# LDO.net
KiCad netlist of a schematic drawn in Altium Designer
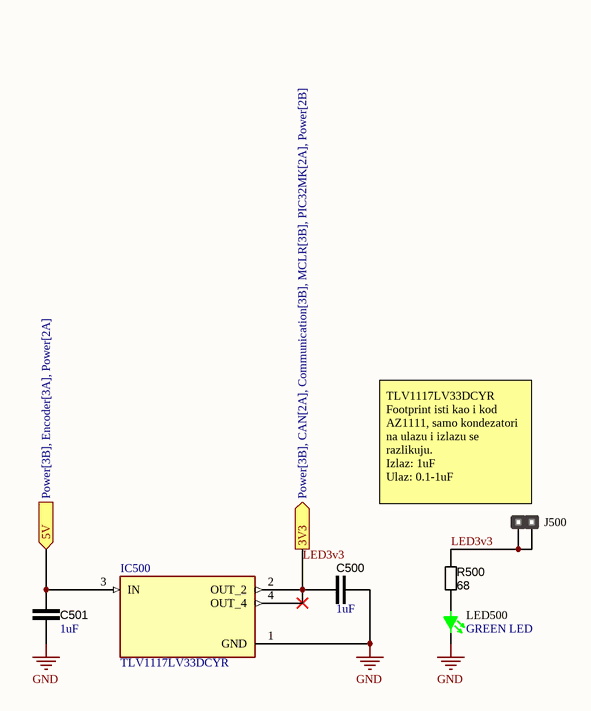
[diagram p0: LDO.SchDoc]

(export (version "E")
  (design (tool "Eeschema 10.0.6"))
  (components
    (comp (ref "C500")
      (value "1uF")
      (footprint "CAP_1206")
      (description "1 µF ±10% 25V Ceramic Capacitor X5R 1206 (3216 Metric)")
      (fields (field (name "DIGIKEY PART NUMBER") "1276-3047-1-ND"))
      (libsource (lib "") (part "C000020_1"))
    )
    (comp (ref "C501")
      (value "1uF")
      (footprint "CAP_1206")
      (description "1 µF ±10% 25V Ceramic Capacitor X5R 1206 (3216 Metric)")
      (fields (field (name "DIGIKEY PART NUMBER") "1276-3047-1-ND"))
      (libsource (lib "CapacitorsIntegrated") (part "C000020"))
    )
    (comp (ref "IC500")
      (value "TLV1117LV33DCYR")
      (footprint "VREG_TLV1117LV33DCYR")
      (description "1-A, low-dropout voltage regulator 4-SOT-223 -40 to 125")
      (fields (field (name "MF") "{'manufacturer': u'Texas Instruments'}"))
      (libsource (lib "SnapEDA_Library2") (part "TLV1117LV33DCYR"))
    )
    (comp (ref "J500") (value "*") (footprint "HM1x2") (libsource (lib "motion_board") (part "HEADER_1x2")))
    (comp (ref "LED500")
      (value "GREEN LED")
      (footprint "DIOC1608X04N")
      (description "LED GREEN DIFFUSED 0603 SMD")
      (libsource (lib "Miscellaneous_Lib1") (part "00000001"))
    )
    (comp (ref "R500")
      (value "68")
      (footprint "RES_0603")
      (description "RES 68 OHM 1% 1/10W 0603")
      (libsource (lib "ResistorsIntegrated") (part "R000004"))
    )
  )
  (nets
    (net (code "1") (name "/5V") (class "Default")
      (node (ref "C501") (pin "1") (pinfunction "1_1") (pintype "passive"))
      (node (ref "IC500") (pin "3") (pinfunction "IN_3") (pintype "input"))
    )
    (net (code "2") (name "/LED3v3") (class "Default")
      (node (ref "C500") (pin "2") (pinfunction "2_2") (pintype "passive"))
      (node (ref "IC500") (pin "2") (pinfunction "OUT_2_2") (pintype "output"))
      (node (ref "IC500") (pin "4") (pinfunction "OUT_4_4") (pintype "output"))
      (node (ref "J500") (pin "1") (pinfunction "1_1") (pintype "passive"))
      (node (ref "J500") (pin "2") (pinfunction "1_2") (pintype "passive"))
      (node (ref "R500") (pin "2") (pinfunction "2_2") (pintype "passive"))
    )
    (net (code "3") (name "GND") (class "Default")
      (node (ref "C500") (pin "1") (pinfunction "1_1") (pintype "passive"))
      (node (ref "C501") (pin "2") (pinfunction "2_2") (pintype "passive"))
      (node (ref "IC500") (pin "1") (pinfunction "GND_1") (pintype "power_in"))
      (node (ref "LED500") (pin "2") (pinfunction "2_2") (pintype "passive"))
    )
    (net (code "4") (name "Net-(LED500-Pad1)") (class "Default")
      (node (ref "LED500") (pin "1") (pinfunction "1_1") (pintype "passive"))
      (node (ref "R500") (pin "1") (pinfunction "1_1") (pintype "passive"))
    )
  )
)
